# menlo_cnc_de10.net
KiCad netlist of a schematic drawn in EAGLE
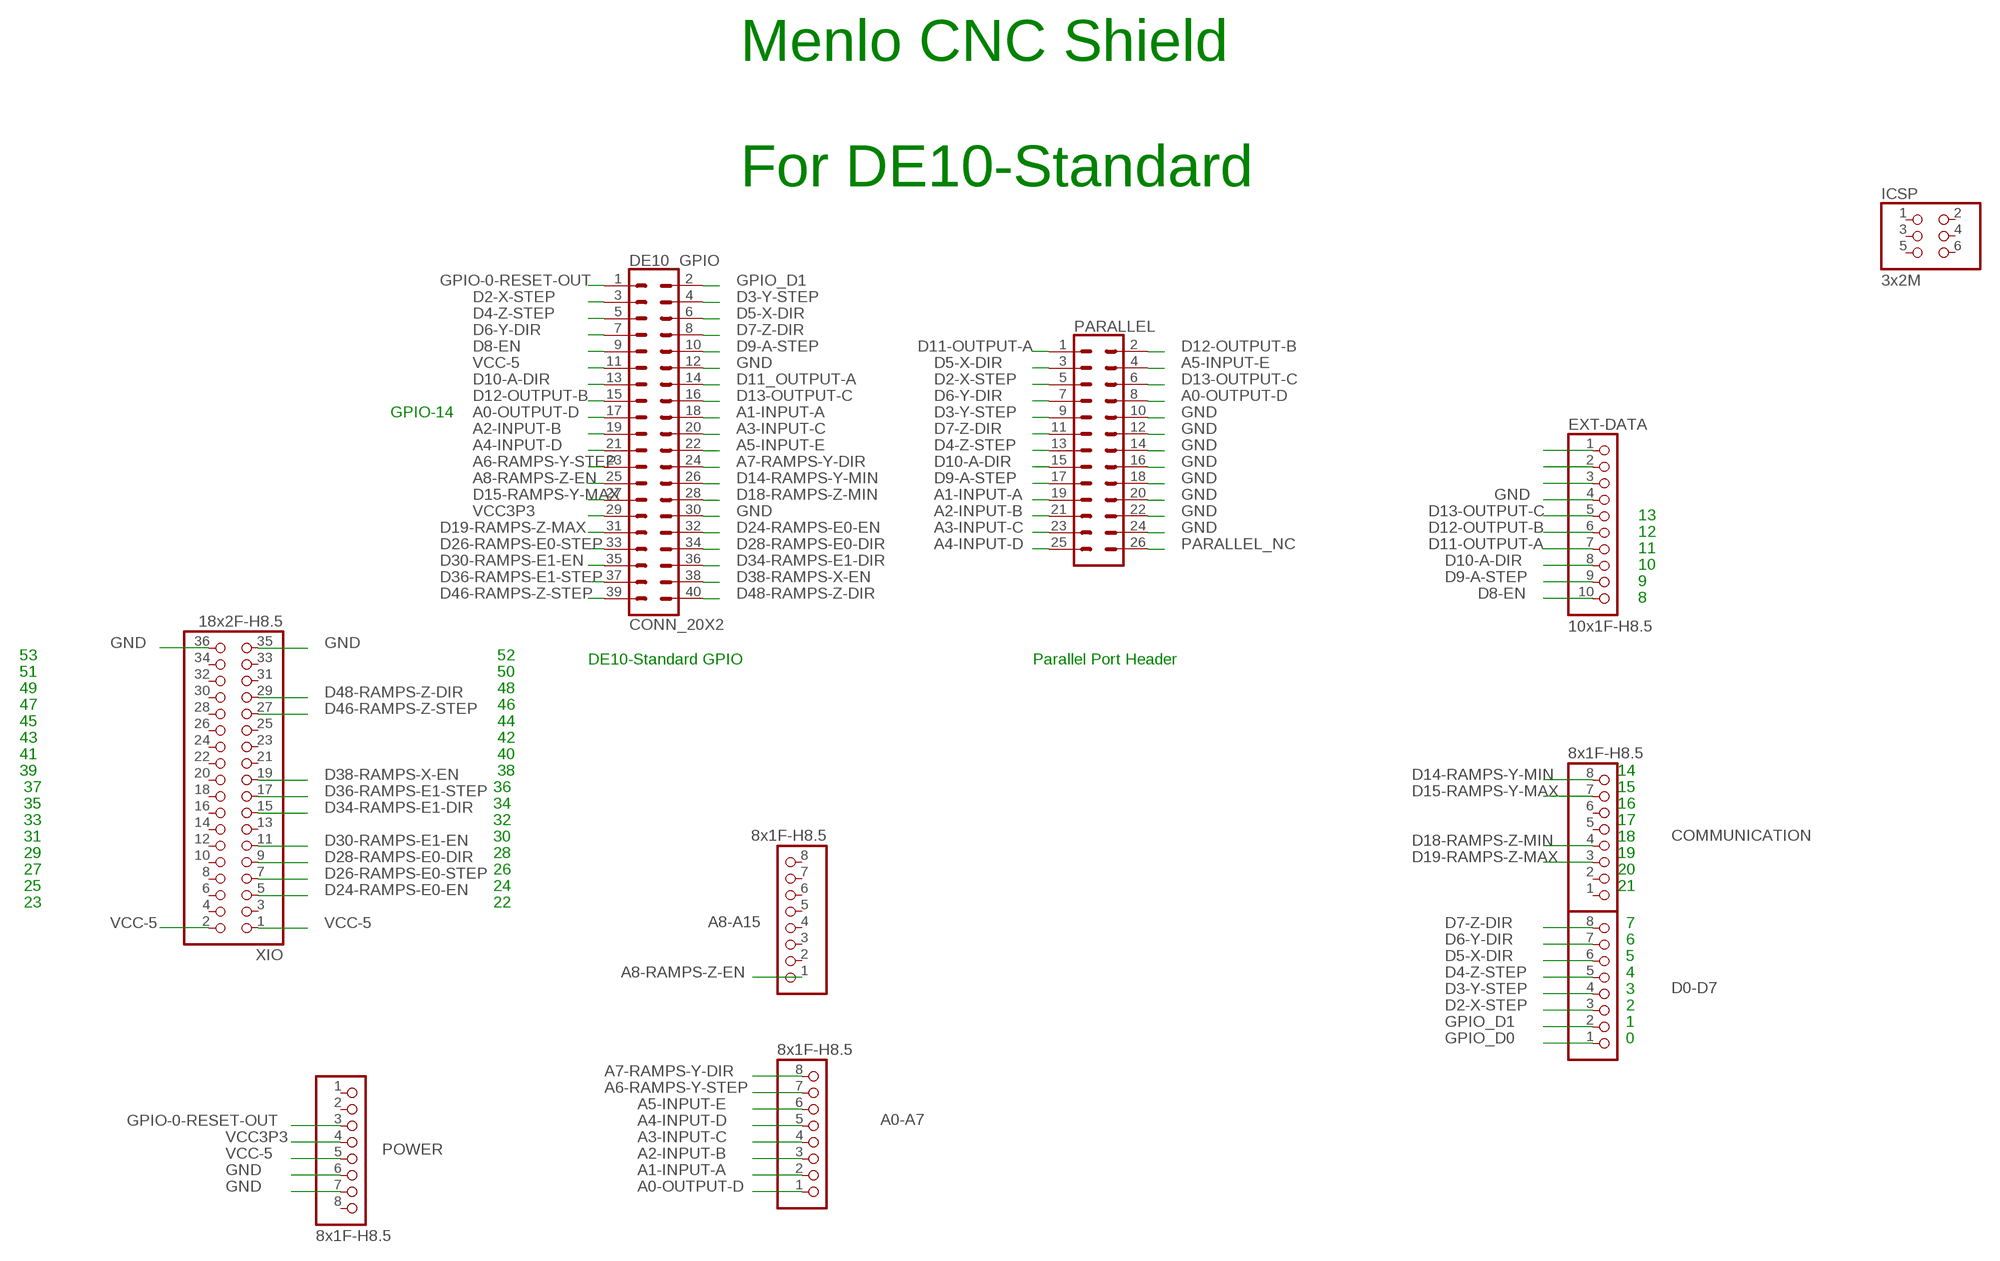
[diagram p0: schematic, sheet 1]

(export (version "E")
  (design (tool "Eeschema 10.0.6"))
  (components
    (comp (ref "A0-A7")
      (value "8x1F-H8.5")
      (footprint "eagle-import:1X08")
      (libsource (lib "eagle-import") (part "PINHD-1X8"))
    )
    (comp (ref "A8-A15")
      (value "8x1F-H8.5")
      (footprint "eagle-import:1X08")
      (libsource (lib "eagle-import") (part "PINHD-1X8"))
    )
    (comp (ref "COMMUNICATION")
      (value "8x1F-H8.5")
      (footprint "eagle-import:1X08")
      (libsource (lib "eagle-import") (part "PINHD-1X8"))
    )
    (comp (ref "D0-D7")
      (value "8x1F-H8.5")
      (footprint "eagle-import:1X08")
      (libsource (lib "eagle-import") (part "PINHD-1X8"))
    )
    (comp (ref "DE10_GPIO")
      (value "CONN_20X2")
      (footprint "eagle-import:2X20")
      (libsource (lib "eagle-import") (part "CONN_20X2"))
    )
    (comp (ref "EXT-DATA")
      (value "10x1F-H8.5")
      (footprint "eagle-import:1X10")
      (libsource (lib "eagle-import") (part "PINHD-1X10_ARD"))
    )
    (comp (ref "ICSP")
      (value "3x2M")
      (footprint "eagle-import:2X03")
      (libsource (lib "eagle-import") (part "PINHD-2X3"))
    )
    (comp (ref "PARALLEL")
      (value "CONN_13X22X13")
      (footprint "eagle-import:2X13")
      (libsource (lib "eagle-import") (part "CONN_13X22X13"))
    )
    (comp (ref "POWER")
      (value "8x1F-H8.5")
      (footprint "eagle-import:1X08")
      (libsource (lib "eagle-import") (part "PINHD-1X8"))
    )
    (comp (ref "XIO")
      (value "18x2F-H8.5")
      (footprint "eagle-import:2X18")
      (libsource (lib "eagle-import") (part "PINHD-2X18"))
    )
  )
  (nets
    (net (code "1") (name "/A0-OUTPUT-D") (class "Default")
      (node (ref "A0-A7") (pin "1") (pinfunction "1_1") (pintype "passive"))
      (node (ref "DE10_GPIO") (pin "17") (pinfunction "17_17") (pintype "passive"))
      (node (ref "PARALLEL") (pin "8") (pinfunction "8_8") (pintype "passive"))
    )
    (net (code "2") (name "/A1-INPUT-A") (class "Default")
      (node (ref "A0-A7") (pin "2") (pinfunction "2_2") (pintype "passive"))
      (node (ref "DE10_GPIO") (pin "18") (pinfunction "18_18") (pintype "passive"))
      (node (ref "PARALLEL") (pin "19") (pinfunction "19_19") (pintype "passive"))
    )
    (net (code "3") (name "/A2-INPUT-B") (class "Default")
      (node (ref "A0-A7") (pin "3") (pinfunction "3_3") (pintype "passive"))
      (node (ref "DE10_GPIO") (pin "19") (pinfunction "19_19") (pintype "passive"))
      (node (ref "PARALLEL") (pin "21") (pinfunction "21_21") (pintype "passive"))
    )
    (net (code "4") (name "/A3-INPUT-C") (class "Default")
      (node (ref "A0-A7") (pin "4") (pinfunction "4_4") (pintype "passive"))
      (node (ref "DE10_GPIO") (pin "20") (pinfunction "20_20") (pintype "passive"))
      (node (ref "PARALLEL") (pin "23") (pinfunction "23_23") (pintype "passive"))
    )
    (net (code "5") (name "/A4-INPUT-D") (class "Default")
      (node (ref "A0-A7") (pin "5") (pinfunction "5_5") (pintype "passive"))
      (node (ref "DE10_GPIO") (pin "21") (pinfunction "21_21") (pintype "passive"))
      (node (ref "PARALLEL") (pin "25") (pinfunction "25_25") (pintype "passive"))
    )
    (net (code "6") (name "/A5-INPUT-E") (class "Default")
      (node (ref "A0-A7") (pin "6") (pinfunction "6_6") (pintype "passive"))
      (node (ref "DE10_GPIO") (pin "22") (pinfunction "22_22") (pintype "passive"))
      (node (ref "PARALLEL") (pin "4") (pinfunction "4_4") (pintype "passive"))
    )
    (net (code "7") (name "/A6-RAMPS-Y-STEP") (class "Default")
      (node (ref "A0-A7") (pin "7") (pinfunction "7_7") (pintype "passive"))
      (node (ref "DE10_GPIO") (pin "23") (pinfunction "23_23") (pintype "passive"))
    )
    (net (code "8") (name "/A7-RAMPS-Y-DIR") (class "Default")
      (node (ref "A0-A7") (pin "8") (pinfunction "8_8") (pintype "passive"))
      (node (ref "DE10_GPIO") (pin "24") (pinfunction "24_24") (pintype "passive"))
    )
    (net (code "9") (name "/A8-RAMPS-Z-EN") (class "Default")
      (node (ref "A8-A15") (pin "1") (pinfunction "1_1") (pintype "passive"))
      (node (ref "DE10_GPIO") (pin "25") (pinfunction "25_25") (pintype "passive"))
    )
    (net (code "10") (name "/D2-X-STEP") (class "Default")
      (node (ref "D0-D7") (pin "3") (pinfunction "3_3") (pintype "passive"))
      (node (ref "DE10_GPIO") (pin "3") (pinfunction "3_3") (pintype "passive"))
      (node (ref "PARALLEL") (pin "5") (pinfunction "5_5") (pintype "passive"))
    )
    (net (code "11") (name "/D3-Y-STEP") (class "Default")
      (node (ref "D0-D7") (pin "4") (pinfunction "4_4") (pintype "passive"))
      (node (ref "DE10_GPIO") (pin "4") (pinfunction "4_4") (pintype "passive"))
      (node (ref "PARALLEL") (pin "9") (pinfunction "9_9") (pintype "passive"))
    )
    (net (code "12") (name "/D4-Z-STEP") (class "Default")
      (node (ref "D0-D7") (pin "5") (pinfunction "5_5") (pintype "passive"))
      (node (ref "DE10_GPIO") (pin "5") (pinfunction "5_5") (pintype "passive"))
      (node (ref "PARALLEL") (pin "13") (pinfunction "13_13") (pintype "passive"))
    )
    (net (code "13") (name "/D5-X-DIR") (class "Default")
      (node (ref "D0-D7") (pin "6") (pinfunction "6_6") (pintype "passive"))
      (node (ref "DE10_GPIO") (pin "6") (pinfunction "6_6") (pintype "passive"))
      (node (ref "PARALLEL") (pin "3") (pinfunction "3_3") (pintype "passive"))
    )
    (net (code "14") (name "/D6-Y-DIR") (class "Default")
      (node (ref "D0-D7") (pin "7") (pinfunction "7_7") (pintype "passive"))
      (node (ref "DE10_GPIO") (pin "7") (pinfunction "7_7") (pintype "passive"))
      (node (ref "PARALLEL") (pin "7") (pinfunction "7_7") (pintype "passive"))
    )
    (net (code "15") (name "/D7-Z-DIR") (class "Default")
      (node (ref "D0-D7") (pin "8") (pinfunction "8_8") (pintype "passive"))
      (node (ref "DE10_GPIO") (pin "8") (pinfunction "8_8") (pintype "passive"))
      (node (ref "PARALLEL") (pin "11") (pinfunction "11_11") (pintype "passive"))
    )
    (net (code "16") (name "/D8-EN") (class "Default")
      (node (ref "DE10_GPIO") (pin "9") (pinfunction "9_9") (pintype "passive"))
      (node (ref "EXT-DATA") (pin "10") (pinfunction "10_10") (pintype "passive"))
    )
    (net (code "17") (name "/D9-A-STEP") (class "Default")
      (node (ref "DE10_GPIO") (pin "10") (pinfunction "10_10") (pintype "passive"))
      (node (ref "EXT-DATA") (pin "9") (pinfunction "9_9") (pintype "passive"))
      (node (ref "PARALLEL") (pin "17") (pinfunction "17_17") (pintype "passive"))
    )
    (net (code "18") (name "/D10-A-DIR") (class "Default")
      (node (ref "DE10_GPIO") (pin "13") (pinfunction "13_13") (pintype "passive"))
      (node (ref "EXT-DATA") (pin "8") (pinfunction "8_8") (pintype "passive"))
      (node (ref "PARALLEL") (pin "15") (pinfunction "15_15") (pintype "passive"))
    )
    (net (code "19") (name "/D11-OUTPUT-A") (class "Default")
      (node (ref "EXT-DATA") (pin "7") (pinfunction "7_7") (pintype "passive"))
      (node (ref "PARALLEL") (pin "1") (pinfunction "1_1") (pintype "passive"))
    )
    (net (code "20") (name "/D11_OUTPUT-A") (class "Default")
      (node (ref "DE10_GPIO") (pin "14") (pinfunction "14_14") (pintype "passive"))
    )
    (net (code "21") (name "/D12-OUTPUT-B") (class "Default")
      (node (ref "DE10_GPIO") (pin "15") (pinfunction "15_15") (pintype "passive"))
      (node (ref "EXT-DATA") (pin "6") (pinfunction "6_6") (pintype "passive"))
      (node (ref "PARALLEL") (pin "2") (pinfunction "2_2") (pintype "passive"))
    )
    (net (code "22") (name "/D13-OUTPUT-C") (class "Default")
      (node (ref "DE10_GPIO") (pin "16") (pinfunction "16_16") (pintype "passive"))
      (node (ref "EXT-DATA") (pin "5") (pinfunction "5_5") (pintype "passive"))
      (node (ref "PARALLEL") (pin "6") (pinfunction "6_6") (pintype "passive"))
    )
    (net (code "23") (name "/D14-RAMPS-Y-MIN") (class "Default")
      (node (ref "COMMUNICATION") (pin "8") (pinfunction "8_8") (pintype "passive"))
      (node (ref "DE10_GPIO") (pin "26") (pinfunction "26_26") (pintype "passive"))
    )
    (net (code "24") (name "/D15-RAMPS-Y-MAX") (class "Default")
      (node (ref "COMMUNICATION") (pin "7") (pinfunction "7_7") (pintype "passive"))
      (node (ref "DE10_GPIO") (pin "27") (pinfunction "27_27") (pintype "passive"))
    )
    (net (code "25") (name "/D18-RAMPS-Z-MIN") (class "Default")
      (node (ref "COMMUNICATION") (pin "4") (pinfunction "4_4") (pintype "passive"))
      (node (ref "DE10_GPIO") (pin "28") (pinfunction "28_28") (pintype "passive"))
    )
    (net (code "26") (name "/D19-RAMPS-Z-MAX") (class "Default")
      (node (ref "COMMUNICATION") (pin "3") (pinfunction "3_3") (pintype "passive"))
      (node (ref "DE10_GPIO") (pin "31") (pinfunction "31_31") (pintype "passive"))
    )
    (net (code "27") (name "/D24-RAMPS-E0-EN") (class "Default")
      (node (ref "DE10_GPIO") (pin "32") (pinfunction "32_32") (pintype "passive"))
      (node (ref "XIO") (pin "5") (pinfunction "5_5") (pintype "passive"))
    )
    (net (code "28") (name "/D26-RAMPS-E0-STEP") (class "Default")
      (node (ref "DE10_GPIO") (pin "33") (pinfunction "33_33") (pintype "passive"))
      (node (ref "XIO") (pin "7") (pinfunction "7_7") (pintype "passive"))
    )
    (net (code "29") (name "/D28-RAMPS-E0-DIR") (class "Default")
      (node (ref "DE10_GPIO") (pin "34") (pinfunction "34_34") (pintype "passive"))
      (node (ref "XIO") (pin "9") (pinfunction "9_9") (pintype "passive"))
    )
    (net (code "30") (name "/D30-RAMPS-E1-EN") (class "Default")
      (node (ref "DE10_GPIO") (pin "35") (pinfunction "35_35") (pintype "passive"))
      (node (ref "XIO") (pin "11") (pinfunction "11_11") (pintype "passive"))
    )
    (net (code "31") (name "/D34-RAMPS-E1-DIR") (class "Default")
      (node (ref "DE10_GPIO") (pin "36") (pinfunction "36_36") (pintype "passive"))
      (node (ref "XIO") (pin "15") (pinfunction "15_15") (pintype "passive"))
    )
    (net (code "32") (name "/D36-RAMPS-E1-STEP") (class "Default")
      (node (ref "DE10_GPIO") (pin "37") (pinfunction "37_37") (pintype "passive"))
      (node (ref "XIO") (pin "17") (pinfunction "17_17") (pintype "passive"))
    )
    (net (code "33") (name "/D38-RAMPS-X-EN") (class "Default")
      (node (ref "DE10_GPIO") (pin "38") (pinfunction "38_38") (pintype "passive"))
      (node (ref "XIO") (pin "19") (pinfunction "19_19") (pintype "passive"))
    )
    (net (code "34") (name "/D46-RAMPS-Z-STEP") (class "Default")
      (node (ref "DE10_GPIO") (pin "39") (pinfunction "39_39") (pintype "passive"))
      (node (ref "XIO") (pin "27") (pinfunction "27_27") (pintype "passive"))
    )
    (net (code "35") (name "/D48-RAMPS-Z-DIR") (class "Default")
      (node (ref "DE10_GPIO") (pin "40") (pinfunction "40_40") (pintype "passive"))
      (node (ref "XIO") (pin "29") (pinfunction "29_29") (pintype "passive"))
    )
    (net (code "36") (name "/GND") (class "Default")
      (node (ref "DE10_GPIO") (pin "12") (pinfunction "12_12") (pintype "passive"))
      (node (ref "DE10_GPIO") (pin "30") (pinfunction "30_30") (pintype "passive"))
      (node (ref "EXT-DATA") (pin "4") (pinfunction "4_4") (pintype "passive"))
      (node (ref "PARALLEL") (pin "10") (pinfunction "10_10") (pintype "passive"))
      (node (ref "PARALLEL") (pin "12") (pinfunction "12_12") (pintype "passive"))
      (node (ref "PARALLEL") (pin "14") (pinfunction "14_14") (pintype "passive"))
      (node (ref "PARALLEL") (pin "16") (pinfunction "16_16") (pintype "passive"))
      (node (ref "PARALLEL") (pin "18") (pinfunction "18_18") (pintype "passive"))
      (node (ref "PARALLEL") (pin "20") (pinfunction "20_20") (pintype "passive"))
      (node (ref "PARALLEL") (pin "22") (pinfunction "22_22") (pintype "passive"))
      (node (ref "PARALLEL") (pin "24") (pinfunction "24_24") (pintype "passive"))
      (node (ref "POWER") (pin "6") (pinfunction "6_6") (pintype "passive"))
      (node (ref "POWER") (pin "7") (pinfunction "7_7") (pintype "passive"))
      (node (ref "XIO") (pin "35") (pinfunction "35_35") (pintype "passive"))
      (node (ref "XIO") (pin "36") (pinfunction "36_36") (pintype "passive"))
    )
    (net (code "37") (name "/GPIO-0-RESET-OUT") (class "Default")
      (node (ref "DE10_GPIO") (pin "1") (pinfunction "1_1") (pintype "passive"))
      (node (ref "POWER") (pin "3") (pinfunction "3_3") (pintype "passive"))
    )
    (net (code "38") (name "/GPIO_D0") (class "Default")
      (node (ref "D0-D7") (pin "1") (pinfunction "1_1") (pintype "passive"))
    )
    (net (code "39") (name "/GPIO_D1") (class "Default")
      (node (ref "D0-D7") (pin "2") (pinfunction "2_2") (pintype "passive"))
      (node (ref "DE10_GPIO") (pin "2") (pinfunction "2_2") (pintype "passive"))
    )
    (net (code "40") (name "/PARALLEL_NC") (class "Default")
      (node (ref "PARALLEL") (pin "26") (pinfunction "26_26") (pintype "passive"))
    )
    (net (code "41") (name "/VCC-5") (class "Default")
      (node (ref "DE10_GPIO") (pin "11") (pinfunction "11_11") (pintype "passive"))
      (node (ref "POWER") (pin "5") (pinfunction "5_5") (pintype "passive"))
      (node (ref "XIO") (pin "1") (pinfunction "1_1") (pintype "passive"))
      (node (ref "XIO") (pin "2") (pinfunction "2_2") (pintype "passive"))
    )
    (net (code "42") (name "/VCC3P3") (class "Default")
      (node (ref "DE10_GPIO") (pin "29") (pinfunction "29_29") (pintype "passive"))
      (node (ref "POWER") (pin "4") (pinfunction "4_4") (pintype "passive"))
    )
    (net (code "43") (name "unconnected-(A8-A15-Pad2)") (class "Default")
      (node (ref "A8-A15") (pin "2") (pinfunction "2_2") (pintype "passive"))
    )
    (net (code "44") (name "unconnected-(A8-A15-Pad3)") (class "Default")
      (node (ref "A8-A15") (pin "3") (pinfunction "3_3") (pintype "passive"))
    )
    (net (code "45") (name "unconnected-(A8-A15-Pad4)") (class "Default")
      (node (ref "A8-A15") (pin "4") (pinfunction "4_4") (pintype "passive"))
    )
    (net (code "46") (name "unconnected-(A8-A15-Pad5)") (class "Default")
      (node (ref "A8-A15") (pin "5") (pinfunction "5_5") (pintype "passive"))
    )
    (net (code "47") (name "unconnected-(A8-A15-Pad6)") (class "Default")
      (node (ref "A8-A15") (pin "6") (pinfunction "6_6") (pintype "passive"))
    )
    (net (code "48") (name "unconnected-(A8-A15-Pad7)") (class "Default")
      (node (ref "A8-A15") (pin "7") (pinfunction "7_7") (pintype "passive"))
    )
    (net (code "49") (name "unconnected-(A8-A15-Pad8)") (class "Default")
      (node (ref "A8-A15") (pin "8") (pinfunction "8_8") (pintype "passive"))
    )
    (net (code "50") (name "unconnected-(COMMUNICATION-Pad1)") (class "Default")
      (node (ref "COMMUNICATION") (pin "1") (pinfunction "1_1") (pintype "passive"))
    )
    (net (code "51") (name "unconnected-(COMMUNICATION-Pad2)") (class "Default")
      (node (ref "COMMUNICATION") (pin "2") (pinfunction "2_2") (pintype "passive"))
    )
    (net (code "52") (name "unconnected-(COMMUNICATION-Pad5)") (class "Default")
      (node (ref "COMMUNICATION") (pin "5") (pinfunction "5_5") (pintype "passive"))
    )
    (net (code "53") (name "unconnected-(COMMUNICATION-Pad6)") (class "Default")
      (node (ref "COMMUNICATION") (pin "6") (pinfunction "6_6") (pintype "passive"))
    )
    (net (code "54") (name "unconnected-(EXT-DATA-Pad1)") (class "Default")
      (node (ref "EXT-DATA") (pin "1") (pinfunction "1_1") (pintype "passive"))
    )
    (net (code "55") (name "unconnected-(EXT-DATA-Pad2)") (class "Default")
      (node (ref "EXT-DATA") (pin "2") (pinfunction "2_2") (pintype "passive"))
    )
    (net (code "56") (name "unconnected-(EXT-DATA-Pad3)") (class "Default")
      (node (ref "EXT-DATA") (pin "3") (pinfunction "3_3") (pintype "passive"))
    )
    (net (code "57") (name "unconnected-(ICSP-Pad1)") (class "Default")
      (node (ref "ICSP") (pin "1") (pinfunction "1_1") (pintype "passive"))
    )
    (net (code "58") (name "unconnected-(ICSP-Pad2)") (class "Default")
      (node (ref "ICSP") (pin "2") (pinfunction "2_2") (pintype "passive"))
    )
    (net (code "59") (name "unconnected-(ICSP-Pad3)") (class "Default")
      (node (ref "ICSP") (pin "3") (pinfunction "3_3") (pintype "passive"))
    )
    (net (code "60") (name "unconnected-(ICSP-Pad4)") (class "Default")
      (node (ref "ICSP") (pin "4") (pinfunction "4_4") (pintype "passive"))
    )
    (net (code "61") (name "unconnected-(ICSP-Pad5)") (class "Default")
      (node (ref "ICSP") (pin "5") (pinfunction "5_5") (pintype "passive"))
    )
    (net (code "62") (name "unconnected-(ICSP-Pad6)") (class "Default")
      (node (ref "ICSP") (pin "6") (pinfunction "6_6") (pintype "passive"))
    )
    (net (code "63") (name "unconnected-(POWER-Pad1)") (class "Default")
      (node (ref "POWER") (pin "1") (pinfunction "1_1") (pintype "passive"))
    )
    (net (code "64") (name "unconnected-(POWER-Pad2)") (class "Default")
      (node (ref "POWER") (pin "2") (pinfunction "2_2") (pintype "passive"))
    )
    (net (code "65") (name "unconnected-(POWER-Pad8)") (class "Default")
      (node (ref "POWER") (pin "8") (pinfunction "8_8") (pintype "passive"))
    )
    (net (code "66") (name "unconnected-(XIO-Pad3)") (class "Default")
      (node (ref "XIO") (pin "3") (pinfunction "3_3") (pintype "passive"))
    )
    (net (code "67") (name "unconnected-(XIO-Pad4)") (class "Default")
      (node (ref "XIO") (pin "4") (pinfunction "4_4") (pintype "passive"))
    )
    (net (code "68") (name "unconnected-(XIO-Pad6)") (class "Default")
      (node (ref "XIO") (pin "6") (pinfunction "6_6") (pintype "passive"))
    )
    (net (code "69") (name "unconnected-(XIO-Pad8)") (class "Default")
      (node (ref "XIO") (pin "8") (pinfunction "8_8") (pintype "passive"))
    )
    (net (code "70") (name "unconnected-(XIO-Pad10)") (class "Default")
      (node (ref "XIO") (pin "10") (pinfunction "10_10") (pintype "passive"))
    )
    (net (code "71") (name "unconnected-(XIO-Pad12)") (class "Default")
      (node (ref "XIO") (pin "12") (pinfunction "12_12") (pintype "passive"))
    )
    (net (code "72") (name "unconnected-(XIO-Pad13)") (class "Default")
      (node (ref "XIO") (pin "13") (pinfunction "13_13") (pintype "passive"))
    )
    (net (code "73") (name "unconnected-(XIO-Pad14)") (class "Default")
      (node (ref "XIO") (pin "14") (pinfunction "14_14") (pintype "passive"))
    )
    (net (code "74") (name "unconnected-(XIO-Pad16)") (class "Default")
      (node (ref "XIO") (pin "16") (pinfunction "16_16") (pintype "passive"))
    )
    (net (code "75") (name "unconnected-(XIO-Pad18)") (class "Default")
      (node (ref "XIO") (pin "18") (pinfunction "18_18") (pintype "passive"))
    )
    (net (code "76") (name "unconnected-(XIO-Pad20)") (class "Default")
      (node (ref "XIO") (pin "20") (pinfunction "20_20") (pintype "passive"))
    )
    (net (code "77") (name "unconnected-(XIO-Pad21)") (class "Default")
      (node (ref "XIO") (pin "21") (pinfunction "21_21") (pintype "passive"))
    )
    (net (code "78") (name "unconnected-(XIO-Pad22)") (class "Default")
      (node (ref "XIO") (pin "22") (pinfunction "22_22") (pintype "passive"))
    )
    (net (code "79") (name "unconnected-(XIO-Pad23)") (class "Default")
      (node (ref "XIO") (pin "23") (pinfunction "23_23") (pintype "passive"))
    )
    (net (code "80") (name "unconnected-(XIO-Pad24)") (class "Default")
      (node (ref "XIO") (pin "24") (pinfunction "24_24") (pintype "passive"))
    )
    (net (code "81") (name "unconnected-(XIO-Pad25)") (class "Default")
      (node (ref "XIO") (pin "25") (pinfunction "25_25") (pintype "passive"))
    )
    (net (code "82") (name "unconnected-(XIO-Pad26)") (class "Default")
      (node (ref "XIO") (pin "26") (pinfunction "26_26") (pintype "passive"))
    )
    (net (code "83") (name "unconnected-(XIO-Pad28)") (class "Default")
      (node (ref "XIO") (pin "28") (pinfunction "28_28") (pintype "passive"))
    )
    (net (code "84") (name "unconnected-(XIO-Pad30)") (class "Default")
      (node (ref "XIO") (pin "30") (pinfunction "30_30") (pintype "passive"))
    )
    (net (code "85") (name "unconnected-(XIO-Pad31)") (class "Default")
      (node (ref "XIO") (pin "31") (pinfunction "31_31") (pintype "passive"))
    )
    (net (code "86") (name "unconnected-(XIO-Pad32)") (class "Default")
      (node (ref "XIO") (pin "32") (pinfunction "32_32") (pintype "passive"))
    )
    (net (code "87") (name "unconnected-(XIO-Pad33)") (class "Default")
      (node (ref "XIO") (pin "33") (pinfunction "33_33") (pintype "passive"))
    )
    (net (code "88") (name "unconnected-(XIO-Pad34)") (class "Default")
      (node (ref "XIO") (pin "34") (pinfunction "34_34") (pintype "passive"))
    )
  )
)
